# SPDT_eval_R2.net
KiCad netlist of a schematic drawn in EAGLE
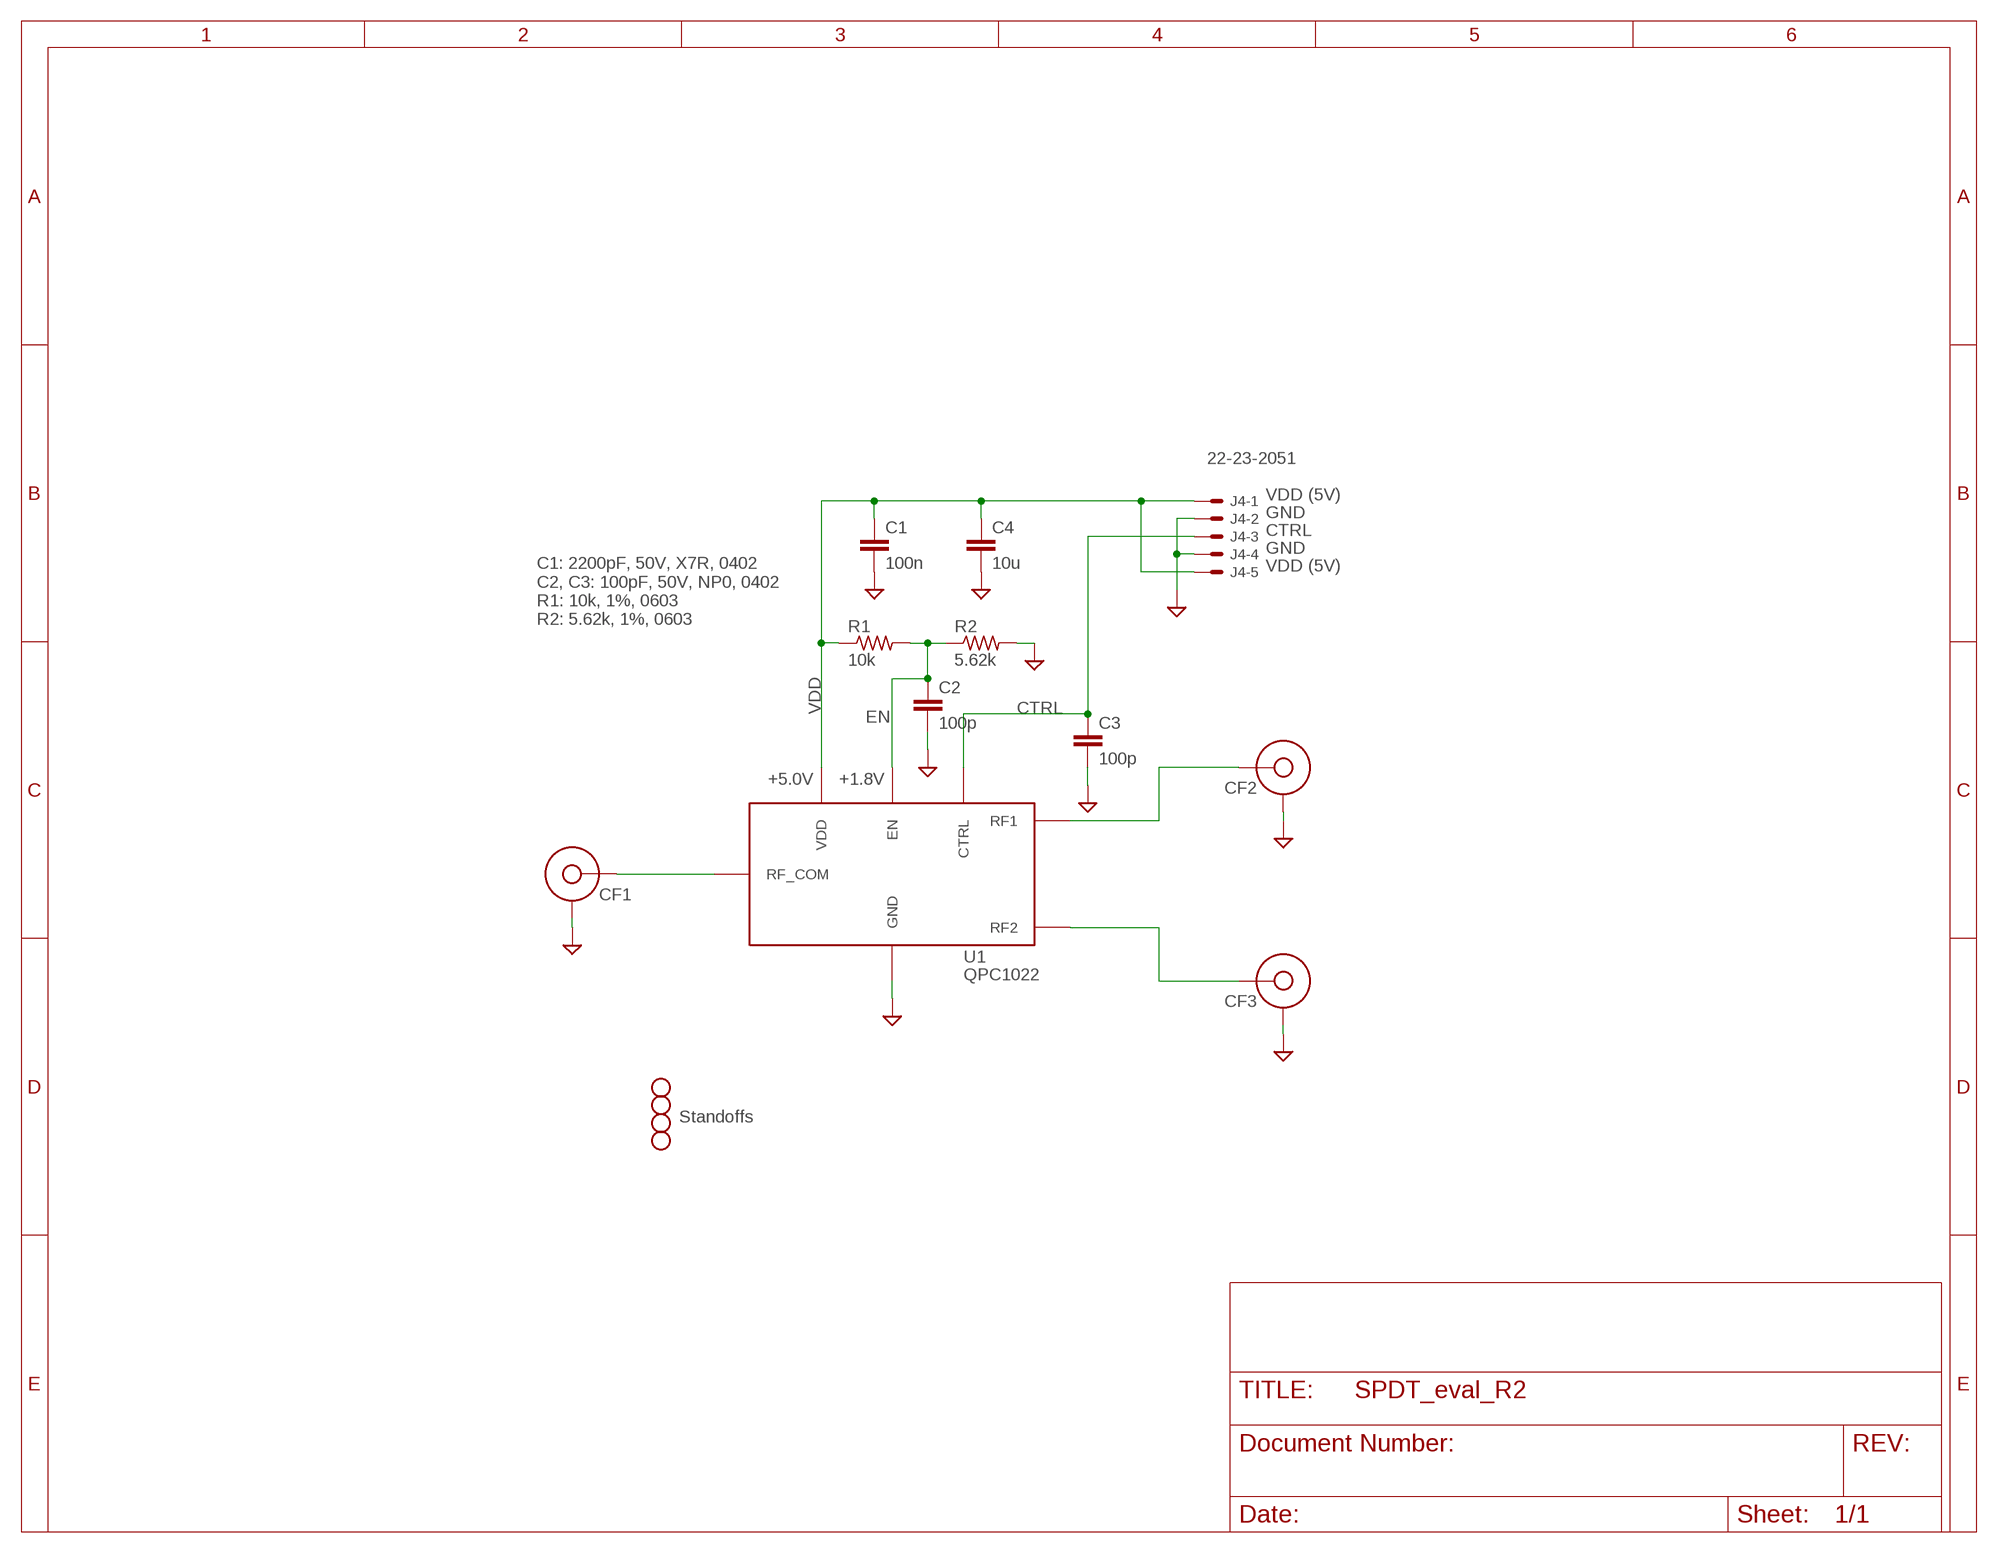
[diagram p0: schematic, sheet 1]

(export (version "E")
  (design (tool "Eeschema 10.0.6"))
  (components
    (comp (ref "C1")
      (value "100n")
      (footprint "eagle-import:.0402-B-NOSILK")
      (libsource (lib "eagle-import") (part "C-EU0402-B-NOSILK"))
    )
    (comp (ref "C2")
      (value "100p")
      (footprint "eagle-import:.0402-B-NOSILK")
      (libsource (lib "eagle-import") (part "C-EU0402-B-NOSILK"))
    )
    (comp (ref "C3")
      (value "100p")
      (footprint "eagle-import:.0402-B-NOSILK")
      (libsource (lib "eagle-import") (part "C-EU0402-B-NOSILK"))
    )
    (comp (ref "C4")
      (value "10u")
      (footprint "eagle-import:.0805-B-NOSILK")
      (libsource (lib "eagle-import") (part "C-EU0805-B-NOSILK"))
    )
    (comp (ref "CF1")
      (value "SMA-CINCH-END-FIRE")
      (footprint "eagle-import:SMAJ716-ND")
      (libsource (lib "eagle-import") (part "SMA-CINCH-END-FIRE"))
    )
    (comp (ref "CF2")
      (value "SMA-CINCH-END-FIRE")
      (footprint "eagle-import:SMAJ716-ND")
      (libsource (lib "eagle-import") (part "SMA-CINCH-END-FIRE"))
    )
    (comp (ref "CF3")
      (value "SMA-CINCH-END-FIRE")
      (footprint "eagle-import:SMAJ716-ND")
      (libsource (lib "eagle-import") (part "SMA-CINCH-END-FIRE"))
    )
    (comp (ref "H1")
      (value "STAND-OFFTIGHT")
      (footprint "eagle-import:STAND-OFF-TIGHT")
      (libsource (lib "eagle-import") (part "STAND-OFFTIGHT"))
    )
    (comp (ref "H2")
      (value "STAND-OFFTIGHT")
      (footprint "eagle-import:STAND-OFF-TIGHT")
      (libsource (lib "eagle-import") (part "STAND-OFFTIGHT"))
    )
    (comp (ref "H3")
      (value "STAND-OFFTIGHT")
      (footprint "eagle-import:STAND-OFF-TIGHT")
      (libsource (lib "eagle-import") (part "STAND-OFFTIGHT"))
    )
    (comp (ref "H4")
      (value "STAND-OFFTIGHT")
      (footprint "eagle-import:STAND-OFF-TIGHT")
      (libsource (lib "eagle-import") (part "STAND-OFFTIGHT"))
    )
    (comp (ref "J4")
      (value "22-23-2051")
      (footprint "eagle-import:22-23-2051")
      (fields (field (name "MF") "MOLEX"))
      (libsource (lib "eagle-import") (part "22-23-2051"))
    )
    (comp (ref "R1")
      (value "10k")
      (footprint "eagle-import:.0603-B-NOSILK")
      (libsource (lib "eagle-import") (part "R-US_0603-B-NOSILK"))
    )
    (comp (ref "R2")
      (value "5.62k")
      (footprint "eagle-import:.0603-B-NOSILK")
      (libsource (lib "eagle-import") (part "R-US_0603-B-NOSILK"))
    )
    (comp (ref "U1")
      (value "QPC1022")
      (footprint "eagle-import:QPC1022")
      (libsource (lib "eagle-import") (part "QPC1022"))
    )
  )
  (nets
    (net (code "1") (name "/CTRL") (class "Default")
      (node (ref "C3") (pin "1") (pinfunction "1_1") (pintype "passive"))
      (node (ref "J4") (pin "3") (pinfunction "S_3") (pintype "passive"))
      (node (ref "U1") (pin "CTRL") (pinfunction "CTRL_CTRL") (pintype "bidirectional"))
    )
    (net (code "2") (name "/EN") (class "Default")
      (node (ref "C2") (pin "1") (pinfunction "1_1") (pintype "passive"))
      (node (ref "R1") (pin "2") (pinfunction "2_2") (pintype "passive"))
      (node (ref "R2") (pin "1") (pinfunction "1_1") (pintype "passive"))
      (node (ref "U1") (pin "EN") (pinfunction "EN_EN") (pintype "bidirectional"))
    )
    (net (code "3") (name "/VDD") (class "Default")
      (node (ref "C1") (pin "1") (pinfunction "1_1") (pintype "passive"))
      (node (ref "C4") (pin "1") (pinfunction "1_1") (pintype "passive"))
      (node (ref "J4") (pin "1") (pinfunction "S_1") (pintype "passive"))
      (node (ref "J4") (pin "5") (pinfunction "S_5") (pintype "passive"))
      (node (ref "R1") (pin "1") (pinfunction "1_1") (pintype "passive"))
      (node (ref "U1") (pin "VDD") (pinfunction "VDD_VDD") (pintype "bidirectional"))
    )
    (net (code "4") (name "GND") (class "Default")
      (node (ref "C1") (pin "2") (pinfunction "2_2") (pintype "passive"))
      (node (ref "C2") (pin "2") (pinfunction "2_2") (pintype "passive"))
      (node (ref "C3") (pin "2") (pinfunction "2_2") (pintype "passive"))
      (node (ref "C4") (pin "2") (pinfunction "2_2") (pintype "passive"))
      (node (ref "CF1") (pin "GND1") (pinfunction "GND_GND1") (pintype "power_in"))
      (node (ref "CF1") (pin "GND2") (pinfunction "GND_GND2") (pintype "power_in"))
      (node (ref "CF1") (pin "GND3") (pinfunction "GND_GND3") (pintype "power_in"))
      (node (ref "CF1") (pin "GND4") (pinfunction "GND_GND4") (pintype "power_in"))
      (node (ref "CF2") (pin "GND1") (pinfunction "GND_GND1") (pintype "power_in"))
      (node (ref "CF2") (pin "GND2") (pinfunction "GND_GND2") (pintype "power_in"))
      (node (ref "CF2") (pin "GND3") (pinfunction "GND_GND3") (pintype "power_in"))
      (node (ref "CF2") (pin "GND4") (pinfunction "GND_GND4") (pintype "power_in"))
      (node (ref "CF3") (pin "GND1") (pinfunction "GND_GND1") (pintype "power_in"))
      (node (ref "CF3") (pin "GND2") (pinfunction "GND_GND2") (pintype "power_in"))
      (node (ref "CF3") (pin "GND3") (pinfunction "GND_GND3") (pintype "power_in"))
      (node (ref "CF3") (pin "GND4") (pinfunction "GND_GND4") (pintype "power_in"))
      (node (ref "J4") (pin "2") (pinfunction "S_2") (pintype "passive"))
      (node (ref "J4") (pin "4") (pinfunction "S_4") (pintype "passive"))
      (node (ref "R2") (pin "2") (pinfunction "2_2") (pintype "passive"))
      (node (ref "U1") (pin "GND@1") (pinfunction "GND_GND@1") (pintype "bidirectional"))
      (node (ref "U1") (pin "GND@2") (pinfunction "GND_GND@2") (pintype "bidirectional"))
      (node (ref "U1") (pin "GND@3") (pinfunction "GND_GND@3") (pintype "bidirectional"))
    )
    (net (code "5") (name "Net-(CF1-CENTERCONDUCTOR)") (class "Default")
      (node (ref "CF1") (pin "P$3") (pinfunction "CENTERCONDUCTOR_P$3") (pintype "bidirectional"))
      (node (ref "U1") (pin "ANT") (pinfunction "RF_COM_ANT") (pintype "bidirectional"))
    )
    (net (code "6") (name "Net-(CF2-CENTERCONDUCTOR)") (class "Default")
      (node (ref "CF2") (pin "P$3") (pinfunction "CENTERCONDUCTOR_P$3") (pintype "bidirectional"))
      (node (ref "U1") (pin "RF1") (pinfunction "RF1_RF1") (pintype "bidirectional"))
    )
    (net (code "7") (name "Net-(CF3-CENTERCONDUCTOR)") (class "Default")
      (node (ref "CF3") (pin "P$3") (pinfunction "CENTERCONDUCTOR_P$3") (pintype "bidirectional"))
      (node (ref "U1") (pin "RF2") (pinfunction "RF2_RF2") (pintype "bidirectional"))
    )
  )
)
